# usb_board_1.net
KiCad netlist of a schematic drawn in Altium Designer
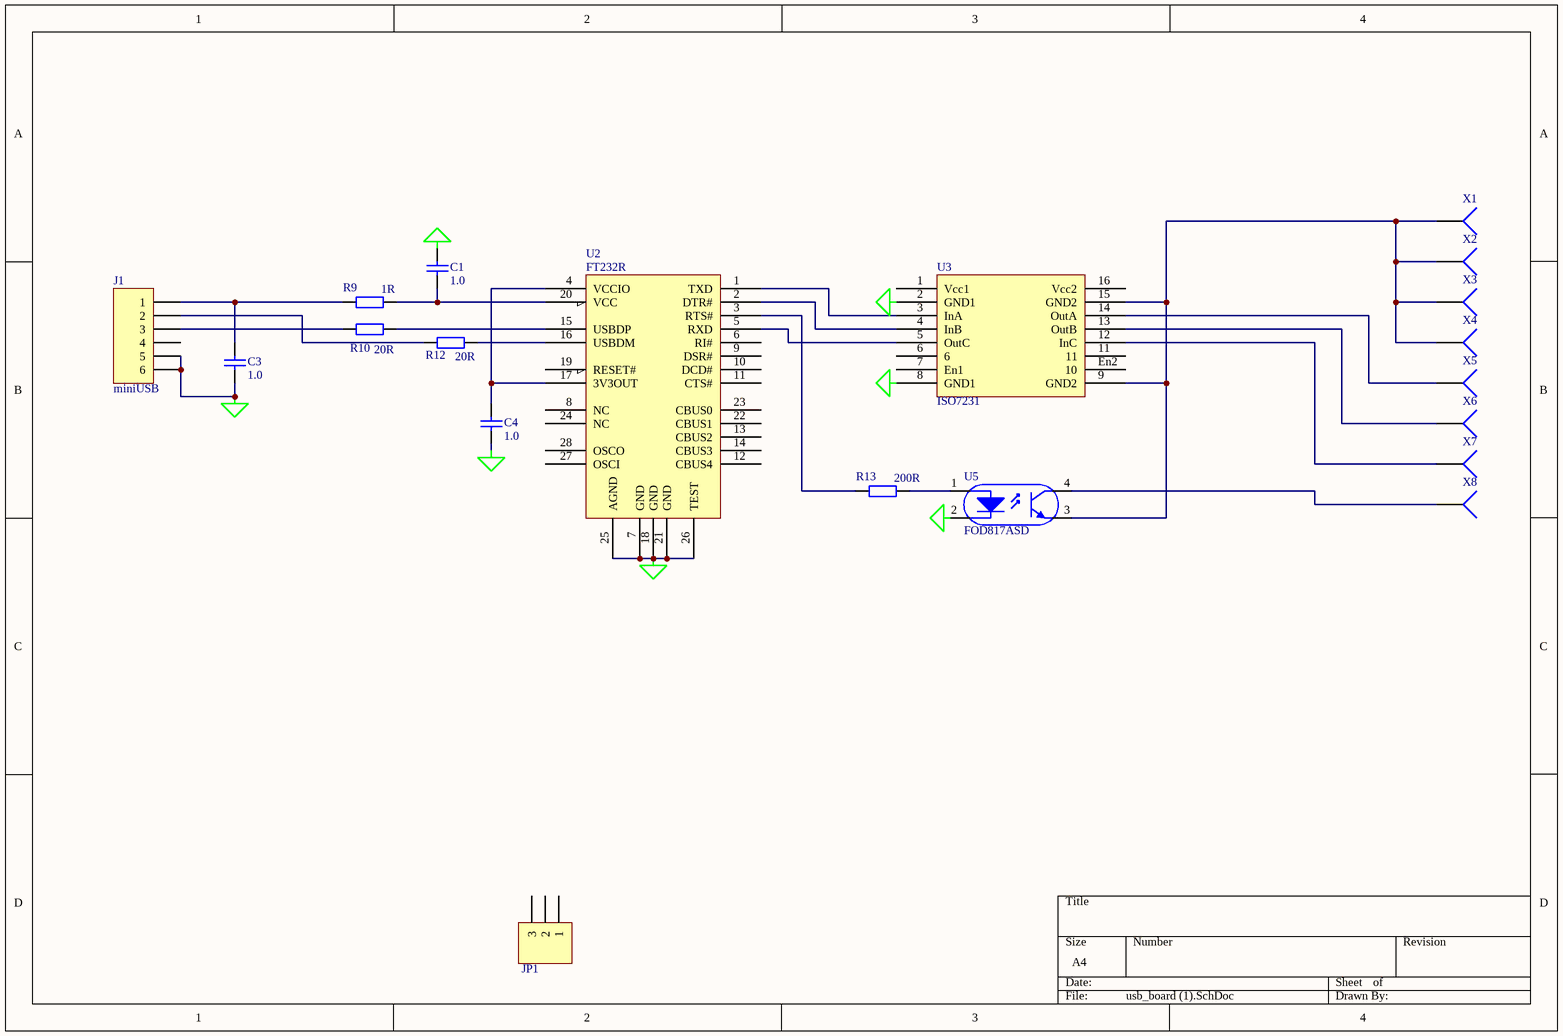
[diagram p0: usb_board (1).SchDoc]

(export (version "E")
  (design (tool "Eeschema 10.0.6"))
  (components
    (comp (ref "C1")
      (value "1.0")
      (footprint "_1206")
      (description "Capacitor (Semiconductor SIM Model)")
      (fields (field (name "MANUFACTURER") "Generic Components") (field (name "PUBLISHER") "Altium Limited"))
      (libsource (lib "Miscellaneous Devices") (part "Cap Semi"))
    )
    (comp (ref "C3")
      (value "1.0")
      (footprint "C3216-1206")
      (description "Capacitor (Semiconductor SIM Model)")
      (fields (field (name "MANUFACTURER") "Generic Components") (field (name "PUBLISHER") "Altium Limited"))
      (libsource (lib "Miscellaneous Devices") (part "Cap Semi"))
    )
    (comp (ref "C4")
      (value "1.0")
      (footprint "C3216-1206")
      (description "Capacitor (Semiconductor SIM Model)")
      (fields (field (name "MANUFACTURER") "Generic Components") (field (name "PUBLISHER") "Altium Limited"))
      (libsource (lib "Miscellaneous Devices") (part "Cap Semi"))
    )
    (comp (ref "J1")
      (value "miniUSB")
      (footprint "USBmini")
      (description "Header, 6-Pin")
      (fields (field (name "PUBLISHER") "Altium Limited"))
      (libsource (lib "Miscellaneous Connectors") (part "Header 6"))
    )
    (comp (ref "JP1")
      (value "PLS-3")
      (footprint "HDR1X3")
      (description "Header, 3-Pin")
      (fields (field (name "MANUFACTURER") "Generic Components") (field (name "PUBLISHER") "Altium Limited"))
      (libsource (lib "Miscellaneous Connectors") (part "Header 3"))
    )
    (comp (ref "R9") (value "1R") (footprint "_1206") (libsource (lib "igorenja") (part "RES")))
    (comp (ref "R10") (value "20R") (footprint "_1206") (libsource (lib "igorenja") (part "RES")))
    (comp (ref "R12") (value "20R") (footprint "_1206") (libsource (lib "igorenja") (part "RES")))
    (comp (ref "R13") (value "200R") (footprint "_1206") (libsource (lib "igorenja") (part "RES")))
    (comp (ref "U2")
      (value "FT232R")
      (footprint "SOP65P780-28L")
      (libsource (lib "igorenja") (part "FT232R"))
    )
    (comp (ref "U3") (value "ISO7231") (footprint "SO-G16/D10.4") (libsource (lib "PAL") (part "ISO7231")))
    (comp (ref "U5") (value "FOD817ASD") (footprint "FOD817ASD") (libsource (lib "PAL") (part "F00817ASD")))
    (comp (ref "X1")
      (value "~")
      (footprint "PIN1")
      (description "Socket")
      (fields (field (name "MANUFACTURER") "Generic Components") (field (name "PUBLISHER") "Altium Limited"))
      (libsource (lib "Miscellaneous Connectors") (part "Socket"))
    )
    (comp (ref "X2")
      (value "~")
      (footprint "PIN1")
      (description "Socket")
      (fields (field (name "MANUFACTURER") "Generic Components") (field (name "PUBLISHER") "Altium Limited"))
      (libsource (lib "Miscellaneous Connectors") (part "Socket"))
    )
    (comp (ref "X3")
      (value "~")
      (footprint "PIN1")
      (description "Socket")
      (fields (field (name "MANUFACTURER") "Generic Components") (field (name "PUBLISHER") "Altium Limited"))
      (libsource (lib "Miscellaneous Connectors") (part "Socket"))
    )
    (comp (ref "X4")
      (value "~")
      (footprint "PIN1")
      (description "Socket")
      (fields (field (name "MANUFACTURER") "Generic Components") (field (name "PUBLISHER") "Altium Limited"))
      (libsource (lib "Miscellaneous Connectors") (part "Socket"))
    )
    (comp (ref "X5")
      (value "~")
      (footprint "PIN1")
      (description "Socket")
      (fields (field (name "MANUFACTURER") "Generic Components") (field (name "PUBLISHER") "Altium Limited"))
      (libsource (lib "Miscellaneous Connectors") (part "Socket"))
    )
    (comp (ref "X6")
      (value "~")
      (footprint "PIN1")
      (description "Socket")
      (fields (field (name "MANUFACTURER") "Generic Components") (field (name "PUBLISHER") "Altium Limited"))
      (libsource (lib "Miscellaneous Connectors") (part "Socket"))
    )
    (comp (ref "X7")
      (value "~")
      (footprint "PIN1")
      (description "Socket")
      (fields (field (name "MANUFACTURER") "Generic Components") (field (name "PUBLISHER") "Altium Limited"))
      (libsource (lib "Miscellaneous Connectors") (part "Socket"))
    )
    (comp (ref "X8")
      (value "~")
      (footprint "PIN1")
      (description "Socket")
      (fields (field (name "MANUFACTURER") "Generic Components") (field (name "PUBLISHER") "Altium Limited"))
      (libsource (lib "Miscellaneous Connectors") (part "Socket"))
    )
  )
  (nets
    (net (code "1") (name "GND_USB") (class "Default")
      (node (ref "C1") (pin "1") (pinfunction "1_1") (pintype "passive"))
      (node (ref "C3") (pin "1") (pinfunction "1_1") (pintype "passive"))
      (node (ref "C4") (pin "1") (pinfunction "1_1") (pintype "passive"))
      (node (ref "J1") (pin "5") (pinfunction "5_5") (pintype "passive"))
      (node (ref "J1") (pin "6") (pinfunction "6_6") (pintype "passive"))
      (node (ref "U2") (pin "18") (pinfunction "GND_18") (pintype "passive"))
      (node (ref "U2") (pin "21") (pinfunction "GND_21") (pintype "passive"))
      (node (ref "U2") (pin "25") (pinfunction "AGND_25") (pintype "passive"))
      (node (ref "U2") (pin "26") (pinfunction "TEST_26") (pintype "passive"))
      (node (ref "U2") (pin "7") (pinfunction "GND_7") (pintype "passive"))
      (node (ref "U3") (pin "2") (pinfunction "GND1_2") (pintype "passive"))
      (node (ref "U3") (pin "8") (pinfunction "GND1_8") (pintype "passive"))
      (node (ref "U5") (pin "2") (pinfunction "1_2") (pintype "passive"))
    )
    (net (code "2") (name "Net-(C3-Pad2)") (class "Default")
      (node (ref "C3") (pin "2") (pinfunction "2_2") (pintype "passive"))
      (node (ref "J1") (pin "1") (pinfunction "1_1") (pintype "passive"))
      (node (ref "R9") (pin "1") (pinfunction "1_1") (pintype "passive"))
    )
    (net (code "3") (name "Net-(J1-Pad2)") (class "Default")
      (node (ref "J1") (pin "2") (pinfunction "2_2") (pintype "passive"))
      (node (ref "R12") (pin "1") (pinfunction "1_1") (pintype "passive"))
    )
    (net (code "4") (name "Net-(J1-Pad3)") (class "Default")
      (node (ref "J1") (pin "3") (pinfunction "3_3") (pintype "passive"))
      (node (ref "R10") (pin "1") (pinfunction "1_1") (pintype "passive"))
    )
    (net (code "5") (name "Net-(U2-3V3OUT)") (class "Default")
      (node (ref "C4") (pin "2") (pinfunction "2_2") (pintype "passive"))
      (node (ref "U2") (pin "17") (pinfunction "3V3OUT_17") (pintype "passive"))
      (node (ref "U2") (pin "4") (pinfunction "VCCIO_4") (pintype "passive"))
    )
    (net (code "6") (name "Net-(U2-DTR#)") (class "Default")
      (node (ref "U2") (pin "2") (pinfunction "DTR#_2") (pintype "passive"))
      (node (ref "U3") (pin "4") (pinfunction "InB_4") (pintype "passive"))
    )
    (net (code "7") (name "Net-(U2-RTS#)") (class "Default")
      (node (ref "R13") (pin "1") (pinfunction "1_1") (pintype "passive"))
      (node (ref "U2") (pin "3") (pinfunction "RTS#_3") (pintype "passive"))
    )
    (net (code "8") (name "Net-(U2-RXD)") (class "Default")
      (node (ref "U2") (pin "5") (pinfunction "RXD_5") (pintype "passive"))
      (node (ref "U3") (pin "5") (pinfunction "OutC_5") (pintype "passive"))
    )
    (net (code "9") (name "Net-(U2-TXD)") (class "Default")
      (node (ref "U2") (pin "1") (pinfunction "TXD_1") (pintype "passive"))
      (node (ref "U3") (pin "3") (pinfunction "InA_3") (pintype "passive"))
    )
    (net (code "10") (name "Net-(U2-USBDM)") (class "Default")
      (node (ref "R12") (pin "2") (pinfunction "2_2") (pintype "passive"))
      (node (ref "U2") (pin "16") (pinfunction "USBDM_16") (pintype "passive"))
    )
    (net (code "11") (name "Net-(U2-USBDP)") (class "Default")
      (node (ref "R10") (pin "2") (pinfunction "2_2") (pintype "passive"))
      (node (ref "U2") (pin "15") (pinfunction "USBDP_15") (pintype "passive"))
    )
    (net (code "12") (name "Net-(U2-VCC)") (class "Default")
      (node (ref "C1") (pin "2") (pinfunction "2_2") (pintype "passive"))
      (node (ref "R9") (pin "2") (pinfunction "2_2") (pintype "passive"))
      (node (ref "U2") (pin "20") (pinfunction "VCC_20") (pintype "passive"))
    )
    (net (code "13") (name "Net-(U3-InC)") (class "Default")
      (node (ref "U3") (pin "12") (pinfunction "InC_12") (pintype "passive"))
      (node (ref "X7") (pin "1") (pinfunction "1_1") (pintype "passive"))
    )
    (net (code "14") (name "Net-(U3-OutA)") (class "Default")
      (node (ref "U3") (pin "14") (pinfunction "OutA_14") (pintype "passive"))
      (node (ref "X5") (pin "1") (pinfunction "1_1") (pintype "passive"))
    )
    (net (code "15") (name "Net-(U3-OutB)") (class "Default")
      (node (ref "U3") (pin "13") (pinfunction "OutB_13") (pintype "passive"))
      (node (ref "X6") (pin "1") (pinfunction "1_1") (pintype "passive"))
    )
    (net (code "16") (name "Net-(U5-0)") (class "Default")
      (node (ref "R13") (pin "2") (pinfunction "2_2") (pintype "passive"))
      (node (ref "U5") (pin "1") (pinfunction "0_1") (pintype "passive"))
    )
    (net (code "17") (name "Net-(U5-2)") (class "Default")
      (node (ref "U5") (pin "4") (pinfunction "2_4") (pintype "passive"))
      (node (ref "X8") (pin "1") (pinfunction "1_1") (pintype "passive"))
    )
    (net (code "18") (name "Net-(U5-4)") (class "Default")
      (node (ref "U3") (pin "15") (pinfunction "GND2_15") (pintype "passive"))
      (node (ref "U3") (pin "9") (pinfunction "GND2_9") (pintype "passive"))
      (node (ref "U5") (pin "3") (pinfunction "4_3") (pintype "passive"))
      (node (ref "X1") (pin "1") (pinfunction "1_1") (pintype "passive"))
      (node (ref "X2") (pin "1") (pinfunction "1_1") (pintype "passive"))
      (node (ref "X3") (pin "1") (pinfunction "1_1") (pintype "passive"))
      (node (ref "X4") (pin "1") (pinfunction "1_1") (pintype "passive"))
    )
    (net (code "19") (name "unconnected-(J1-Pad4)") (class "Default")
      (node (ref "J1") (pin "4") (pinfunction "4_4") (pintype "passive"))
    )
    (net (code "20") (name "unconnected-(JP1-Pad1)") (class "Default")
      (node (ref "JP1") (pin "1") (pinfunction "1_1") (pintype "passive"))
    )
    (net (code "21") (name "unconnected-(JP1-Pad2)") (class "Default")
      (node (ref "JP1") (pin "2") (pinfunction "2_2") (pintype "passive"))
    )
    (net (code "22") (name "unconnected-(JP1-Pad3)") (class "Default")
      (node (ref "JP1") (pin "3") (pinfunction "3_3") (pintype "passive"))
    )
    (net (code "23") (name "unconnected-(U2-CBUS0-Pad23)") (class "Default")
      (node (ref "U2") (pin "23") (pinfunction "CBUS0_23") (pintype "passive"))
    )
    (net (code "24") (name "unconnected-(U2-CBUS1-Pad22)") (class "Default")
      (node (ref "U2") (pin "22") (pinfunction "CBUS1_22") (pintype "passive"))
    )
    (net (code "25") (name "unconnected-(U2-CBUS2-Pad13)") (class "Default")
      (node (ref "U2") (pin "13") (pinfunction "CBUS2_13") (pintype "passive"))
    )
    (net (code "26") (name "unconnected-(U2-CBUS3-Pad14)") (class "Default")
      (node (ref "U2") (pin "14") (pinfunction "CBUS3_14") (pintype "passive"))
    )
    (net (code "27") (name "unconnected-(U2-CBUS4-Pad12)") (class "Default")
      (node (ref "U2") (pin "12") (pinfunction "CBUS4_12") (pintype "passive"))
    )
    (net (code "28") (name "unconnected-(U2-CTS#-Pad11)") (class "Default")
      (node (ref "U2") (pin "11") (pinfunction "CTS#_11") (pintype "passive"))
    )
    (net (code "29") (name "unconnected-(U2-DCD#-Pad10)") (class "Default")
      (node (ref "U2") (pin "10") (pinfunction "DCD#_10") (pintype "passive"))
    )
    (net (code "30") (name "unconnected-(U2-DSR#-Pad9)") (class "Default")
      (node (ref "U2") (pin "9") (pinfunction "DSR#_9") (pintype "passive"))
    )
    (net (code "31") (name "unconnected-(U2-NC-Pad8)") (class "Default")
      (node (ref "U2") (pin "8") (pinfunction "NC_8") (pintype "passive"))
    )
    (net (code "32") (name "unconnected-(U2-NC-Pad24)") (class "Default")
      (node (ref "U2") (pin "24") (pinfunction "NC_24") (pintype "passive"))
    )
    (net (code "33") (name "unconnected-(U2-OSCI-Pad27)") (class "Default")
      (node (ref "U2") (pin "27") (pinfunction "OSCI_27") (pintype "passive"))
    )
    (net (code "34") (name "unconnected-(U2-OSCO-Pad28)") (class "Default")
      (node (ref "U2") (pin "28") (pinfunction "OSCO_28") (pintype "passive"))
    )
    (net (code "35") (name "unconnected-(U2-RESET#-Pad19)") (class "Default")
      (node (ref "U2") (pin "19") (pinfunction "RESET#_19") (pintype "passive"))
    )
    (net (code "36") (name "unconnected-(U2-RI#-Pad6)") (class "Default")
      (node (ref "U2") (pin "6") (pinfunction "RI#_6") (pintype "passive"))
    )
    (net (code "37") (name "unconnected-(U3-10-PadEn2)") (class "Default")
      (node (ref "U3") (pin "En2") (pinfunction "10_En2") (pintype "passive"))
    )
    (net (code "38") (name "unconnected-(U3-En1-Pad7)") (class "Default")
      (node (ref "U3") (pin "7") (pinfunction "En1_7") (pintype "passive"))
    )
    (net (code "39") (name "unconnected-(U3-Pad6)") (class "Default")
      (node (ref "U3") (pin "6") (pinfunction "6_6") (pintype "passive"))
    )
    (net (code "40") (name "unconnected-(U3-Pad11)") (class "Default")
      (node (ref "U3") (pin "11") (pinfunction "11_11") (pintype "passive"))
    )
    (net (code "41") (name "unconnected-(U3-Vcc1-Pad1)") (class "Default")
      (node (ref "U3") (pin "1") (pinfunction "Vcc1_1") (pintype "passive"))
    )
    (net (code "42") (name "unconnected-(U3-Vcc2-Pad16)") (class "Default")
      (node (ref "U3") (pin "16") (pinfunction "Vcc2_16") (pintype "passive"))
    )
  )
)
